# fabflash-mk-2_3-booster.net
KiCad netlist of a schematic drawn in EAGLE
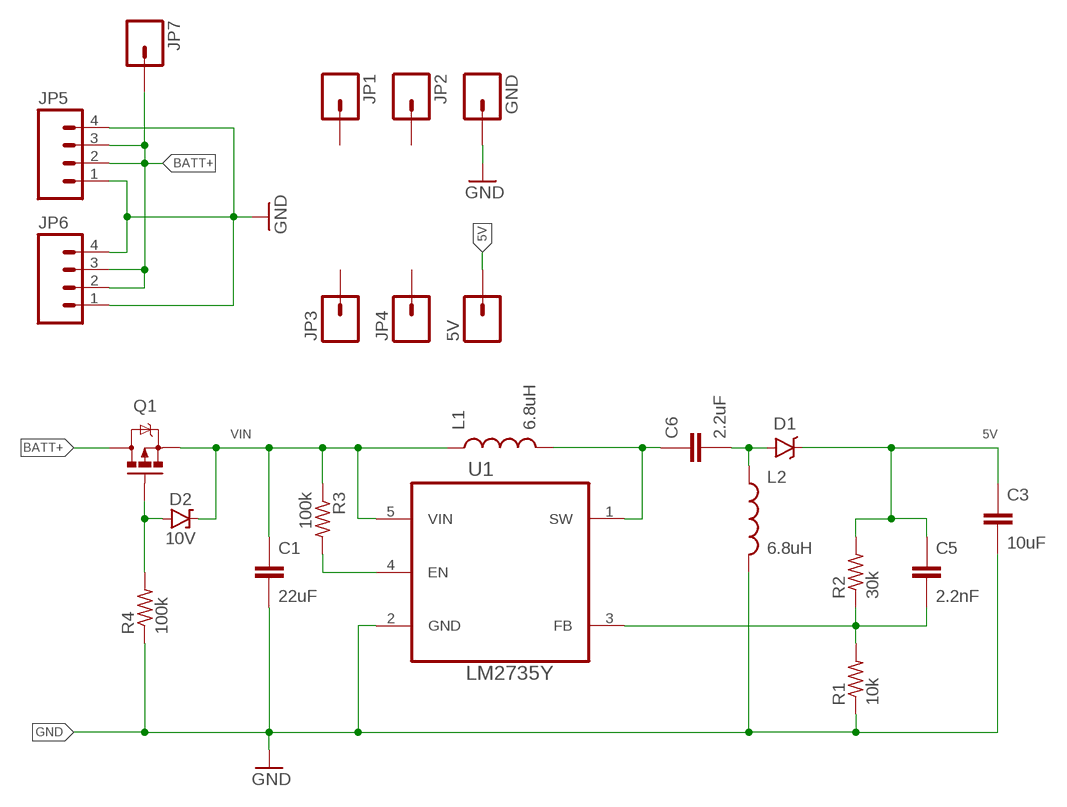
[diagram p0: schematic, sheet 1]

(export (version "E")
  (design (tool "Eeschema 10.0.6"))
  (components
    (comp (ref "5V")
      (value "M01PTH-0.9MM")
      (footprint "eagle-import:1X01-0.9MM")
      (libsource (lib "eagle-import") (part "M01PTH-0.9MM"))
    )
    (comp (ref "C1")
      (value "22uF")
      (footprint "eagle-import:C0805")
      (libsource (lib "eagle-import") (part "CAPACITOR-CERAMICC0805"))
    )
    (comp (ref "C3")
      (value "10uF")
      (footprint "eagle-import:C0805")
      (libsource (lib "eagle-import") (part "CAPACITOR-CERAMICC0805"))
    )
    (comp (ref "C5")
      (value "2.2nF")
      (footprint "eagle-import:C0603")
      (libsource (lib "eagle-import") (part "CAPACITOR-CERAMICC0603"))
    )
    (comp (ref "C6")
      (value "2.2uF")
      (footprint "eagle-import:C0805")
      (libsource (lib "eagle-import") (part "CAPACITOR-CERAMICC0805"))
    )
    (comp (ref "D1")
      (value "B340A")
      (footprint "eagle-import:SMA-DIODE-SCHOTTKY")
      (libsource (lib "eagle-import") (part "DIODE-SCHOTTKYSMA"))
    )
    (comp (ref "D2")
      (value "10V")
      (footprint "eagle-import:SOD123-ZENER")
      (libsource (lib "eagle-import") (part "DIODE-ZENERSOD123"))
    )
    (comp (ref "GND")
      (value "M01PTH-0.9MM")
      (footprint "eagle-import:1X01-0.9MM")
      (libsource (lib "eagle-import") (part "M01PTH-0.9MM"))
    )
    (comp (ref "JP1")
      (value "M01PTH-0.9MM-NS")
      (footprint "eagle-import:1X01-0.9MM-NS")
      (libsource (lib "eagle-import") (part "M01PTH-0.9MM-NS"))
    )
    (comp (ref "JP2")
      (value "M01PTH-0.9MM-NS")
      (footprint "eagle-import:1X01-0.9MM-NS")
      (libsource (lib "eagle-import") (part "M01PTH-0.9MM-NS"))
    )
    (comp (ref "JP3")
      (value "M01PTH-0.9MM-NS")
      (footprint "eagle-import:1X01-0.9MM-NS")
      (libsource (lib "eagle-import") (part "M01PTH-0.9MM-NS"))
    )
    (comp (ref "JP4")
      (value "M01PTH-0.9MM-NS")
      (footprint "eagle-import:1X01-0.9MM-NS")
      (libsource (lib "eagle-import") (part "M01PTH-0.9MM-NS"))
    )
    (comp (ref "JP5")
      (value "M04SMD-SHORT-NS")
      (footprint "eagle-import:1X04-SMD-SHORT")
      (libsource (lib "eagle-import") (part "M04SMD-SHORT-NS"))
    )
    (comp (ref "JP6")
      (value "M04SMD-SHORT-NS")
      (footprint "eagle-import:1X04-SMD-SHORT")
      (libsource (lib "eagle-import") (part "M04SMD-SHORT-NS"))
    )
    (comp (ref "JP7")
      (value "M01NOT-A-VIA-NOPE")
      (footprint "eagle-import:1X01_NOSILK_NOSTOP")
      (libsource (lib "eagle-import") (part "M01NOT-A-VIA-NOPE"))
    )
    (comp (ref "L1")
      (value "6.8uH")
      (footprint "eagle-import:TAIYO-YUDEN-40XX")
      (libsource (lib "eagle-import") (part "INDUCTORTAIYO-YUDEN-40XX"))
    )
    (comp (ref "L2")
      (value "6.8uH")
      (footprint "eagle-import:TAIYO-YUDEN-40XX")
      (libsource (lib "eagle-import") (part "INDUCTORTAIYO-YUDEN-40XX"))
    )
    (comp (ref "Q1")
      (value "MOSFET-PCHANNELIRLML2244")
      (footprint "eagle-import:SOT23-3")
      (libsource (lib "eagle-import") (part "MOSFET-PCHANNELIRLML2244"))
    )
    (comp (ref "R1")
      (value "10k")
      (footprint "eagle-import:R0603")
      (libsource (lib "eagle-import") (part "RESISTORR0603"))
    )
    (comp (ref "R2")
      (value "30k")
      (footprint "eagle-import:R0603")
      (libsource (lib "eagle-import") (part "RESISTORR0603"))
    )
    (comp (ref "R3")
      (value "100k")
      (footprint "eagle-import:R0603")
      (libsource (lib "eagle-import") (part "RESISTORR0603"))
    )
    (comp (ref "R4")
      (value "100k")
      (footprint "eagle-import:R0603")
      (libsource (lib "eagle-import") (part "RESISTORR0603"))
    )
    (comp (ref "U1")
      (value "LM2735Y")
      (footprint "eagle-import:SOT95P285X110-5N")
      (fields (field (name "MPN") "LM2735YMF"))
      (libsource (lib "eagle-import") (part "LM2735YMF"))
    )
  )
  (nets
    (net (code "1") (name "/VIN") (class "Default")
      (node (ref "C1") (pin "1") (pinfunction "1_1") (pintype "passive"))
      (node (ref "D2") (pin "C") (pinfunction "C_C") (pintype "passive"))
      (node (ref "L1") (pin "1") (pinfunction "1_1") (pintype "passive"))
      (node (ref "Q1") (pin "2") (pinfunction "S_2") (pintype "passive"))
      (node (ref "R3") (pin "1") (pinfunction "1_1") (pintype "passive"))
      (node (ref "U1") (pin "5") (pinfunction "VIN_5") (pintype "power_in"))
    )
    (net (code "2") (name "5V") (class "Default")
      (node (ref "5V") (pin "1") (pinfunction "1_1") (pintype "passive"))
      (node (ref "C3") (pin "1") (pinfunction "1_1") (pintype "passive"))
      (node (ref "C5") (pin "1") (pinfunction "1_1") (pintype "passive"))
      (node (ref "D1") (pin "C") (pinfunction "C_C") (pintype "passive"))
      (node (ref "R2") (pin "2") (pinfunction "2_2") (pintype "passive"))
    )
    (net (code "3") (name "BATT+") (class "Default")
      (node (ref "JP5") (pin "2") (pinfunction "2_2") (pintype "passive"))
      (node (ref "JP5") (pin "3") (pinfunction "3_3") (pintype "passive"))
      (node (ref "JP6") (pin "2") (pinfunction "2_2") (pintype "passive"))
      (node (ref "JP6") (pin "3") (pinfunction "3_3") (pintype "passive"))
      (node (ref "JP7") (pin "P$1") (pinfunction "1_P$1") (pintype "passive"))
      (node (ref "Q1") (pin "3") (pinfunction "D_3") (pintype "passive"))
    )
    (net (code "4") (name "GND") (class "Default")
      (node (ref "C1") (pin "2") (pinfunction "2_2") (pintype "passive"))
      (node (ref "C3") (pin "2") (pinfunction "2_2") (pintype "passive"))
      (node (ref "GND") (pin "1") (pinfunction "1_1") (pintype "passive"))
      (node (ref "JP5") (pin "1") (pinfunction "1_1") (pintype "passive"))
      (node (ref "JP5") (pin "4") (pinfunction "4_4") (pintype "passive"))
      (node (ref "JP6") (pin "1") (pinfunction "1_1") (pintype "passive"))
      (node (ref "JP6") (pin "4") (pinfunction "4_4") (pintype "passive"))
      (node (ref "L2") (pin "2") (pinfunction "2_2") (pintype "passive"))
      (node (ref "R1") (pin "1") (pinfunction "1_1") (pintype "passive"))
      (node (ref "R4") (pin "1") (pinfunction "1_1") (pintype "passive"))
      (node (ref "U1") (pin "2") (pinfunction "GND_2") (pintype "power_in"))
    )
    (net (code "5") (name "Net-(C6-Pad2)") (class "Default")
      (node (ref "C6") (pin "2") (pinfunction "2_2") (pintype "passive"))
      (node (ref "D1") (pin "A") (pinfunction "A_A") (pintype "passive"))
      (node (ref "L2") (pin "1") (pinfunction "1_1") (pintype "passive"))
    )
    (net (code "6") (name "Net-(Q1-G)") (class "Default")
      (node (ref "D2") (pin "A") (pinfunction "A_A") (pintype "passive"))
      (node (ref "Q1") (pin "1") (pinfunction "G_1") (pintype "passive"))
      (node (ref "R4") (pin "2") (pinfunction "2_2") (pintype "passive"))
    )
    (net (code "7") (name "Net-(U1-EN)") (class "Default")
      (node (ref "R3") (pin "2") (pinfunction "2_2") (pintype "passive"))
      (node (ref "U1") (pin "4") (pinfunction "EN_4") (pintype "input"))
    )
    (net (code "8") (name "Net-(U1-FB)") (class "Default")
      (node (ref "C5") (pin "2") (pinfunction "2_2") (pintype "passive"))
      (node (ref "R1") (pin "2") (pinfunction "2_2") (pintype "passive"))
      (node (ref "R2") (pin "1") (pinfunction "1_1") (pintype "passive"))
      (node (ref "U1") (pin "3") (pinfunction "FB_3") (pintype "input"))
    )
    (net (code "9") (name "Net-(U1-SW)") (class "Default")
      (node (ref "C6") (pin "1") (pinfunction "1_1") (pintype "passive"))
      (node (ref "L1") (pin "2") (pinfunction "2_2") (pintype "passive"))
      (node (ref "U1") (pin "1") (pinfunction "SW_1") (pintype "power_in"))
    )
    (net (code "10") (name "unconnected-(JP1-Pad1)") (class "Default")
      (node (ref "JP1") (pin "1") (pinfunction "1_1") (pintype "passive"))
    )
    (net (code "11") (name "unconnected-(JP2-Pad1)") (class "Default")
      (node (ref "JP2") (pin "1") (pinfunction "1_1") (pintype "passive"))
    )
    (net (code "12") (name "unconnected-(JP3-Pad1)") (class "Default")
      (node (ref "JP3") (pin "1") (pinfunction "1_1") (pintype "passive"))
    )
    (net (code "13") (name "unconnected-(JP4-Pad1)") (class "Default")
      (node (ref "JP4") (pin "1") (pinfunction "1_1") (pintype "passive"))
    )
  )
)
